# ProDoc_USB-C_Power_Supply_2025-11-02.net
KiCad netlist of a schematic drawn in EasyEDA Pro
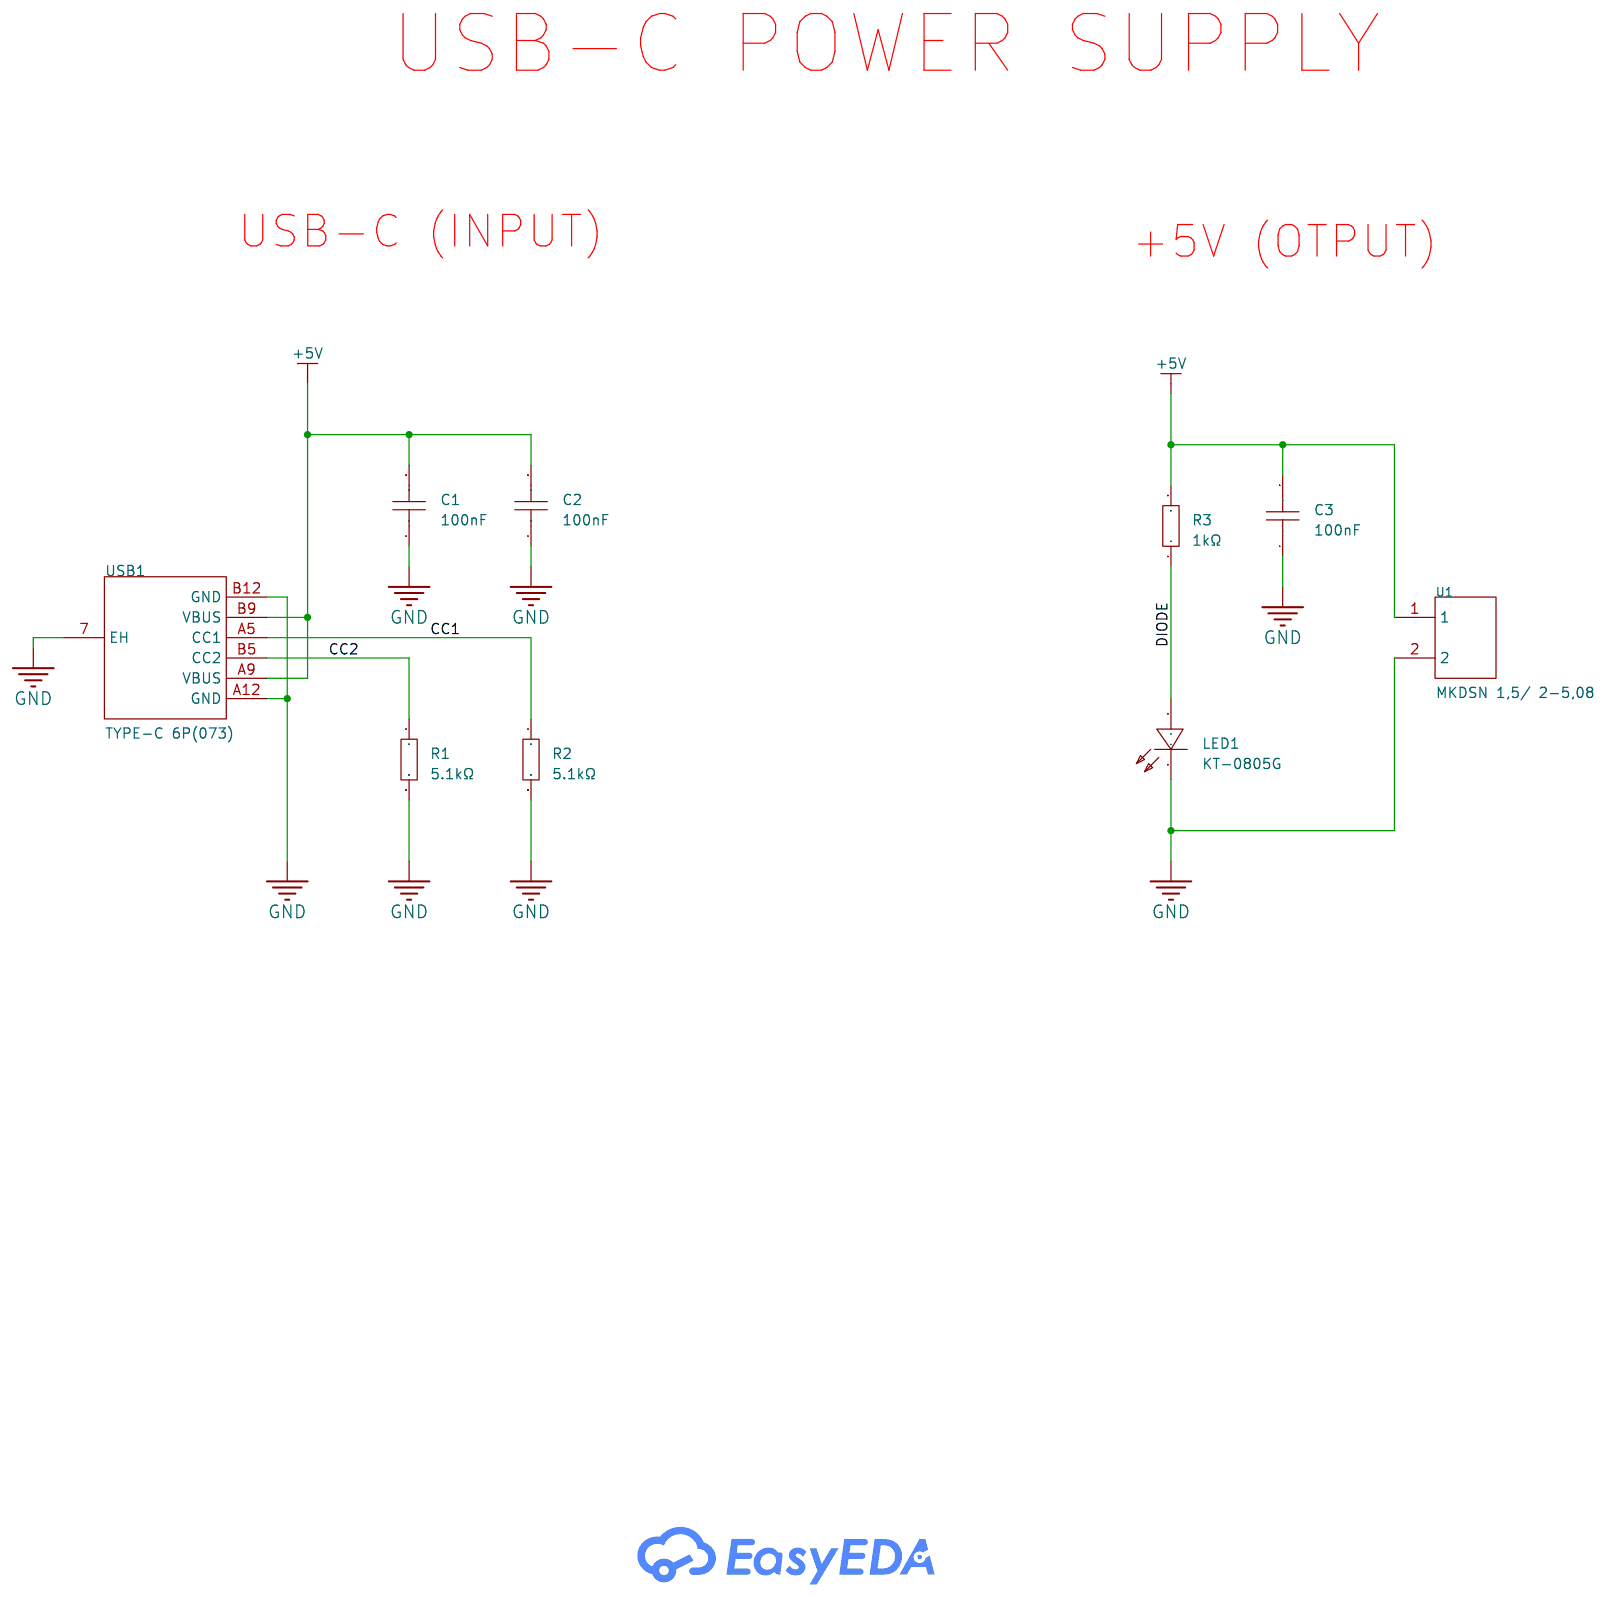
[diagram p0: schematic sheet]

(export (version "E")
  (design (tool "Eeschema 10.0.6"))
  (components
    (comp (ref "C1")
      (value "100nF")
      (footprint "easyedapro:C0805")
      (description "Capacitance:100nF Tolerance:±10% Tolerance:±10% Voltage Rating:50V Temperature Coefficient:X7R")
      (fields
        (field (name "Manufacturer Part") "CC0805KRX7R9BB104")
        (field (name "Manufacturer") "YAGEO(国巨)")
      )
      (libsource (lib "easyedapro") (part "CC0805KRX7R9BB104"))
    )
    (comp (ref "C2")
      (value "100nF")
      (footprint "easyedapro:C0805")
      (description "Capacitance:100nF Tolerance:±10% Tolerance:±10% Voltage Rating:50V Temperature Coefficient:X7R")
      (fields
        (field (name "Manufacturer Part") "CC0805KRX7R9BB104")
        (field (name "Manufacturer") "YAGEO(国巨)")
      )
      (libsource (lib "easyedapro") (part "CC0805KRX7R9BB104"))
    )
    (comp (ref "C3")
      (value "100nF")
      (footprint "easyedapro:C0805")
      (description "Capacitance:100nF Tolerance:±10% Tolerance:±10% Voltage Rating:50V Temperature Coefficient:X7R")
      (fields
        (field (name "Manufacturer Part") "CC0805KRX7R9BB104")
        (field (name "Manufacturer") "YAGEO(国巨)")
      )
      (libsource (lib "easyedapro") (part "CC0805KRX7R9BB104"))
    )
    (comp (ref "LED1")
      (value "KT-0805G")
      (footprint "easyedapro:LED0805-R-RD")
      (fields (field (name "Manufacturer") "KENTO"))
      (libsource (lib "easyedapro") (part "0805G (Green)"))
    )
    (comp (ref "R1")
      (value "5.1kΩ")
      (footprint "easyedapro:R0805")
      (fields
        (field (name "Manufacturer Part") "0805W8F5101T5E")
        (field (name "Manufacturer") "UNI-ROYAL(厚声)")
      )
      (libsource (lib "easyedapro") (part "0805W8F5101T5E"))
    )
    (comp (ref "R2")
      (value "5.1kΩ")
      (footprint "easyedapro:R0805")
      (fields
        (field (name "Manufacturer Part") "0805W8F5101T5E")
        (field (name "Manufacturer") "UNI-ROYAL(厚声)")
      )
      (libsource (lib "easyedapro") (part "0805W8F5101T5E"))
    )
    (comp (ref "R3")
      (value "1kΩ")
      (footprint "easyedapro:R0805")
      (fields
        (field (name "Manufacturer Part") "0805W8F1001T5E")
        (field (name "Manufacturer") "UNI-ROYAL(厚声)")
      )
      (libsource (lib "easyedapro") (part "0805W8F1001T5E"))
    )
    (comp (ref "U1")
      (value "MKDSN 1,5/ 2-5,08")
      (footprint "easyedapro:CONN-TH_2P-P5.08_1729128")
      (fields (field (name "Manufacturer") "Phoenix Contact(菲尼克斯)"))
      (libsource (lib "easyedapro") (part "MKDSN 1,5/ 2-5,08"))
    )
    (comp (ref "USB1")
      (value "TYPE-C 6P(073)")
      (footprint "easyedapro:TYPE-C-SMD_TYPE-C-6P-073")
      (fields (field (name "Manufacturer") "SHOU HAN(首韩)"))
      (libsource (lib "easyedapro") (part "TYPE-C 6P(073)"))
    )
  )
  (nets
    (net (code "1") (name "+5V") (class "Default")
      (node (ref "C1") (pin "2") (pinfunction "2_2") (pintype "unspecified"))
      (node (ref "C2") (pin "2") (pinfunction "2_2") (pintype "unspecified"))
      (node (ref "C3") (pin "2") (pinfunction "2_2") (pintype "unspecified"))
      (node (ref "R3") (pin "2") (pinfunction "2_2") (pintype "input"))
      (node (ref "U1") (pin "1") (pinfunction "1_1") (pintype "input"))
      (node (ref "USB1") (pin "A9") (pinfunction "VBUS_A9") (pintype "unspecified"))
      (node (ref "USB1") (pin "B9") (pinfunction "VBUS_B9") (pintype "unspecified"))
    )
    (net (code "2") (name "/CC1") (class "Default")
      (node (ref "R2") (pin "1") (pinfunction "1_1") (pintype "input"))
      (node (ref "USB1") (pin "A5") (pinfunction "CC1_A5") (pintype "unspecified"))
    )
    (net (code "3") (name "/CC2") (class "Default")
      (node (ref "R1") (pin "1") (pinfunction "1_1") (pintype "input"))
      (node (ref "USB1") (pin "B5") (pinfunction "CC2_B5") (pintype "unspecified"))
    )
    (net (code "4") (name "/DIODE") (class "Default")
      (node (ref "LED1") (pin "1") (pinfunction "A_1") (pintype "unspecified"))
      (node (ref "R3") (pin "1") (pinfunction "1_1") (pintype "input"))
    )
    (net (code "5") (name "GND") (class "Default")
      (node (ref "C1") (pin "1") (pinfunction "1_1") (pintype "unspecified"))
      (node (ref "C2") (pin "1") (pinfunction "1_1") (pintype "unspecified"))
      (node (ref "C3") (pin "1") (pinfunction "1_1") (pintype "unspecified"))
      (node (ref "LED1") (pin "2") (pinfunction "K_2") (pintype "unspecified"))
      (node (ref "R1") (pin "2") (pinfunction "2_2") (pintype "input"))
      (node (ref "R2") (pin "2") (pinfunction "2_2") (pintype "input"))
      (node (ref "U1") (pin "2") (pinfunction "2_2") (pintype "input"))
      (node (ref "USB1") (pin "7") (pinfunction "EH_7") (pintype "unspecified"))
      (node (ref "USB1") (pin "A12") (pinfunction "GND_A12") (pintype "unspecified"))
      (node (ref "USB1") (pin "B12") (pinfunction "GND_B12") (pintype "unspecified"))
    )
  )
)
